# Attiny85_Blinking_Led_FIS2018.net
KiCad netlist of a schematic drawn in EAGLE
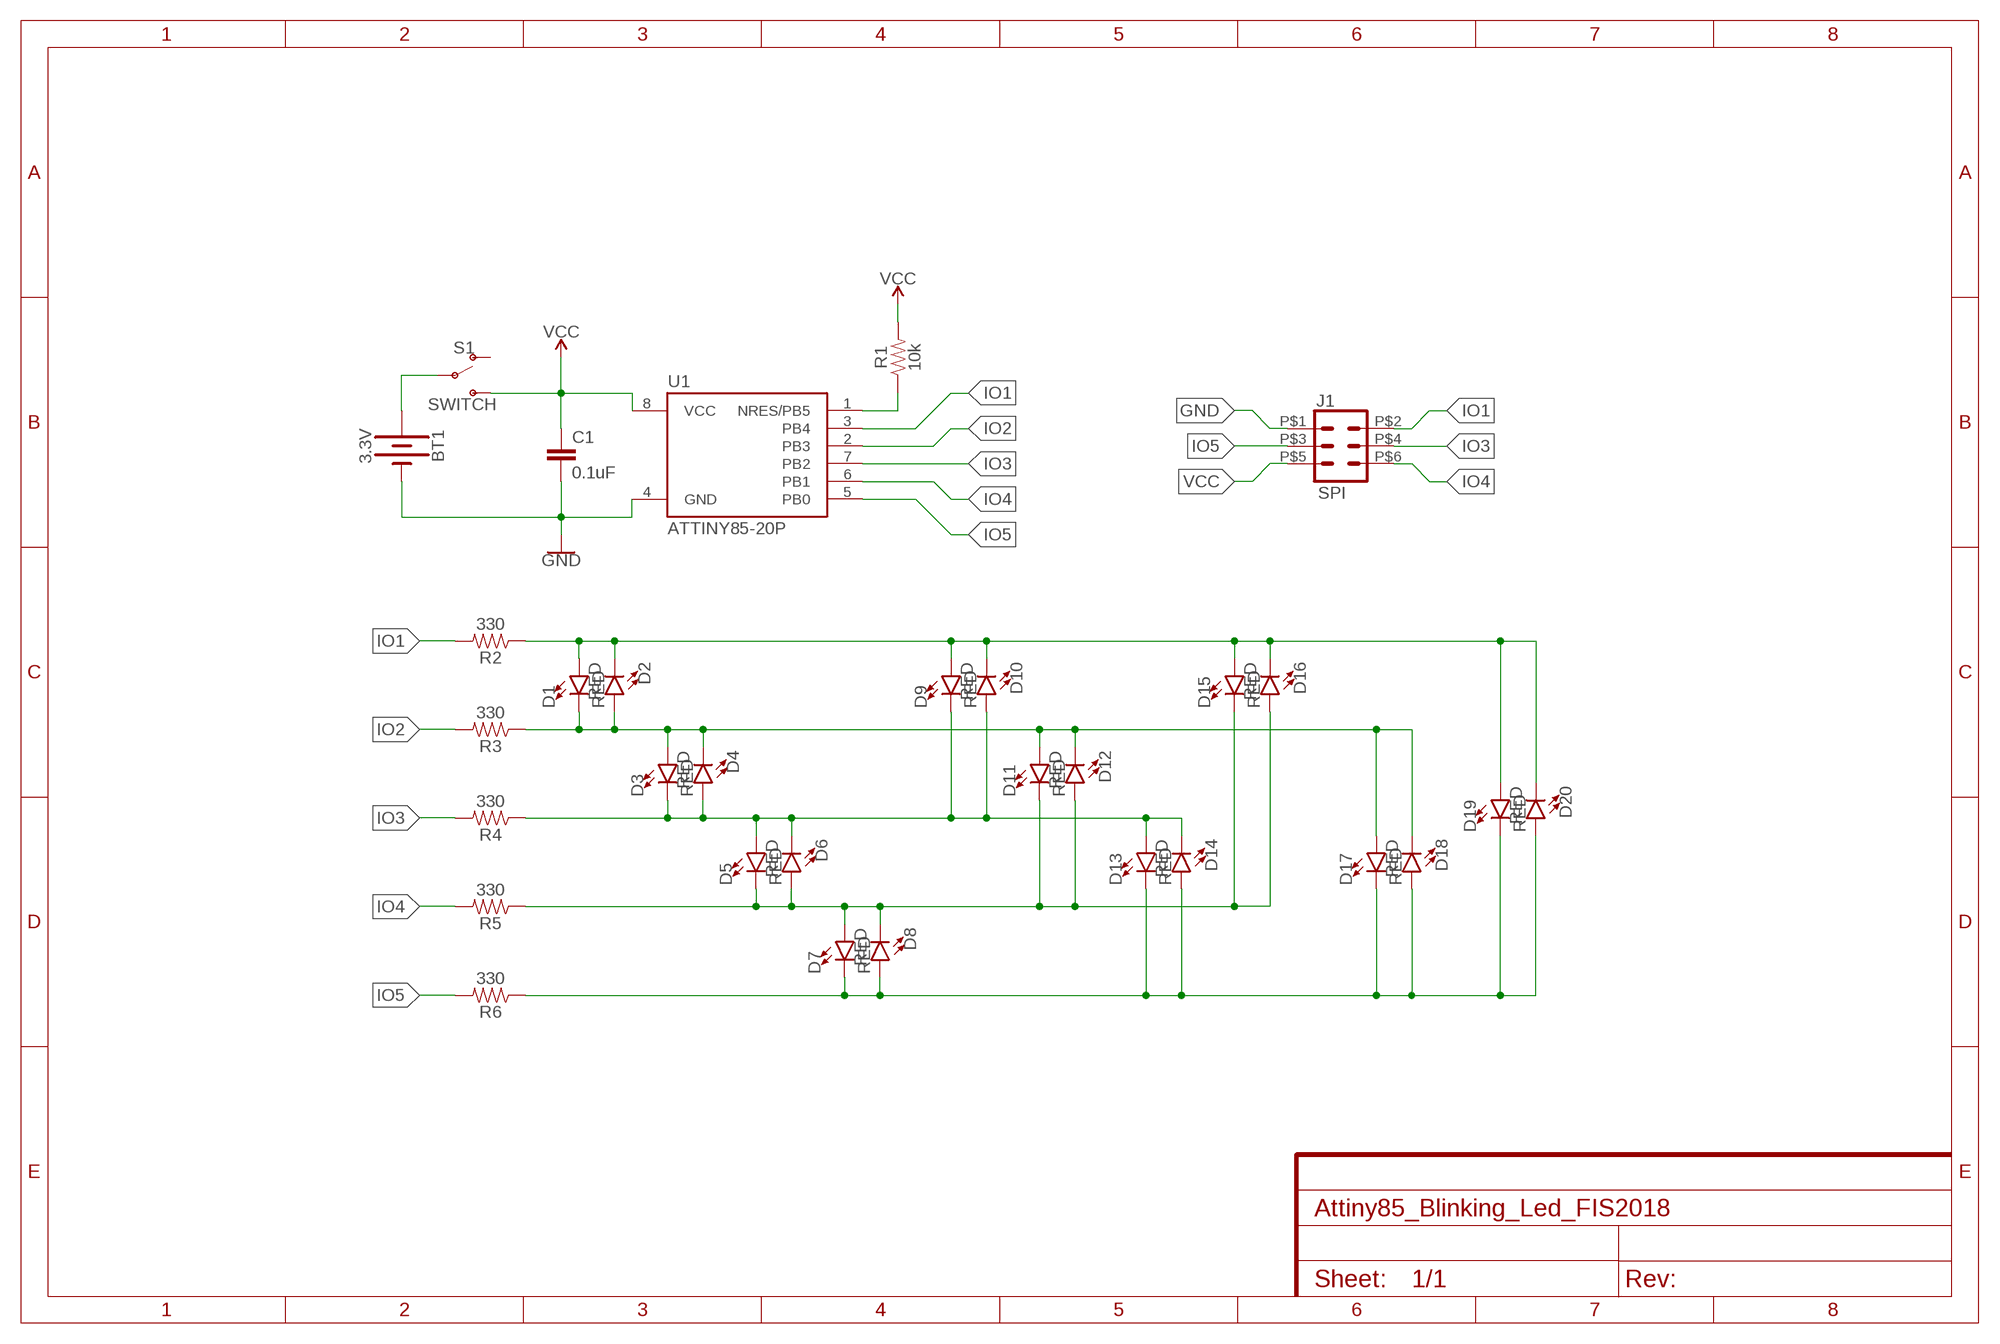
[diagram p0: schematic, sheet 1]

(export (version "E")
  (design (tool "Eeschema 10.0.6"))
  (components
    (comp (ref "BT1")
      (value "3.3V")
      (footprint "eagle-import:BATTCON_20MM_4LEGS")
      (libsource (lib "eagle-import") (part "BATTERY-20MM_SMD_4LEGS"))
    )
    (comp (ref "C1")
      (value "0.1uF")
      (footprint "eagle-import:0603")
      (libsource (lib "eagle-import") (part "0.1UF-0603-25V-(+80/-20%)"))
    )
    (comp (ref "D1")
      (value "RED")
      (footprint "eagle-import:LED_3MM")
      (libsource (lib "eagle-import") (part "LED3MM"))
    )
    (comp (ref "D2")
      (value "RED")
      (footprint "eagle-import:LED_3MM")
      (libsource (lib "eagle-import") (part "LED3MM"))
    )
    (comp (ref "D3")
      (value "RED")
      (footprint "eagle-import:LED_3MM")
      (libsource (lib "eagle-import") (part "LED3MM"))
    )
    (comp (ref "D4")
      (value "RED")
      (footprint "eagle-import:LED_3MM")
      (libsource (lib "eagle-import") (part "LED3MM"))
    )
    (comp (ref "D5")
      (value "RED")
      (footprint "eagle-import:LED_3MM")
      (libsource (lib "eagle-import") (part "LED3MM"))
    )
    (comp (ref "D6")
      (value "RED")
      (footprint "eagle-import:LED_3MM")
      (libsource (lib "eagle-import") (part "LED3MM"))
    )
    (comp (ref "D7")
      (value "RED")
      (footprint "eagle-import:LED_3MM")
      (libsource (lib "eagle-import") (part "LED3MM"))
    )
    (comp (ref "D8")
      (value "RED")
      (footprint "eagle-import:LED_3MM")
      (libsource (lib "eagle-import") (part "LED3MM"))
    )
    (comp (ref "D9")
      (value "RED")
      (footprint "eagle-import:LED_3MM")
      (libsource (lib "eagle-import") (part "LED3MM"))
    )
    (comp (ref "D10")
      (value "RED")
      (footprint "eagle-import:LED_3MM")
      (libsource (lib "eagle-import") (part "LED3MM"))
    )
    (comp (ref "D11")
      (value "RED")
      (footprint "eagle-import:LED_3MM")
      (libsource (lib "eagle-import") (part "LED3MM"))
    )
    (comp (ref "D12")
      (value "RED")
      (footprint "eagle-import:LED_3MM")
      (libsource (lib "eagle-import") (part "LED3MM"))
    )
    (comp (ref "D13")
      (value "RED")
      (footprint "eagle-import:LED_3MM")
      (libsource (lib "eagle-import") (part "LED3MM"))
    )
    (comp (ref "D14")
      (value "RED")
      (footprint "eagle-import:LED_3MM")
      (libsource (lib "eagle-import") (part "LED3MM"))
    )
    (comp (ref "D15")
      (value "RED")
      (footprint "eagle-import:LED_3MM")
      (libsource (lib "eagle-import") (part "LED3MM"))
    )
    (comp (ref "D16")
      (value "RED")
      (footprint "eagle-import:LED_3MM")
      (libsource (lib "eagle-import") (part "LED3MM"))
    )
    (comp (ref "D17")
      (value "RED")
      (footprint "eagle-import:LED_3MM")
      (libsource (lib "eagle-import") (part "LED3MM"))
    )
    (comp (ref "D18")
      (value "RED")
      (footprint "eagle-import:LED_3MM")
      (libsource (lib "eagle-import") (part "LED3MM"))
    )
    (comp (ref "D19")
      (value "RED")
      (footprint "eagle-import:LED_3MM")
      (libsource (lib "eagle-import") (part "LED3MM"))
    )
    (comp (ref "D20")
      (value "RED")
      (footprint "eagle-import:LED_3MM")
      (libsource (lib "eagle-import") (part "LED3MM"))
    )
    (comp (ref "J1")
      (value "SPI")
      (footprint "eagle-import:2X3_POGO")
      (libsource (lib "eagle-import") (part "CONN_03X2POGO_PINS"))
    )
    (comp (ref "R1")
      (value "10k")
      (footprint "eagle-import:AXIAL-0.3")
      (libsource (lib "eagle-import") (part "10KOHM-HORIZ-1/4W-1%"))
    )
    (comp (ref "R2")
      (value "330")
      (footprint "eagle-import:AXIAL-0.3")
      (libsource (lib "eagle-import") (part "10KOHM-HORIZ-1/4W-1%"))
    )
    (comp (ref "R3")
      (value "330")
      (footprint "eagle-import:AXIAL-0.3")
      (libsource (lib "eagle-import") (part "10KOHM-HORIZ-1/4W-1%"))
    )
    (comp (ref "R4")
      (value "330")
      (footprint "eagle-import:AXIAL-0.3")
      (libsource (lib "eagle-import") (part "10KOHM-HORIZ-1/4W-1%"))
    )
    (comp (ref "R5")
      (value "330")
      (footprint "eagle-import:AXIAL-0.3")
      (libsource (lib "eagle-import") (part "10KOHM-HORIZ-1/4W-1%"))
    )
    (comp (ref "R6")
      (value "330")
      (footprint "eagle-import:AXIAL-0.3")
      (libsource (lib "eagle-import") (part "10KOHM-HORIZ-1/4W-1%"))
    )
    (comp (ref "S1")
      (value "SWITCH")
      (footprint "eagle-import:SWITCH_SPST_SMD_A")
      (libsource (lib "eagle-import") (part "SWITCH-SPDT-SMD-RIGHT-ANGLE"))
    )
    (comp (ref "U1")
      (value "ATTINY85-20P")
      (footprint "eagle-import:PDIP08_300MIL")
      (libsource (lib "eagle-import") (part "ATTINY85P-20"))
    )
  )
  (nets
    (net (code "1") (name "GND") (class "Default")
      (node (ref "BT1") (pin "NEGATIVE") (pinfunction "-_NEGATIVE") (pintype "power_in"))
      (node (ref "C1") (pin "2") (pinfunction "2_2") (pintype "passive"))
      (node (ref "J1") (pin "P$1") (pinfunction "1_P$1") (pintype "bidirectional"))
      (node (ref "U1") (pin "4") (pinfunction "GND_4") (pintype "power_in"))
    )
    (net (code "2") (name "IO1") (class "Default")
      (node (ref "J1") (pin "P$2") (pinfunction "2_P$2") (pintype "bidirectional"))
      (node (ref "R2") (pin "P$2") (pinfunction "2_P$2") (pintype "passive"))
      (node (ref "U1") (pin "3") (pinfunction "PB4_3") (pintype "bidirectional"))
    )
    (net (code "3") (name "IO2") (class "Default")
      (node (ref "R3") (pin "P$2") (pinfunction "2_P$2") (pintype "passive"))
      (node (ref "U1") (pin "2") (pinfunction "PB3_2") (pintype "bidirectional"))
    )
    (net (code "4") (name "IO3") (class "Default")
      (node (ref "J1") (pin "P$4") (pinfunction "4_P$4") (pintype "bidirectional"))
      (node (ref "R4") (pin "P$2") (pinfunction "2_P$2") (pintype "passive"))
      (node (ref "U1") (pin "7") (pinfunction "PB2_7") (pintype "bidirectional"))
    )
    (net (code "5") (name "IO4") (class "Default")
      (node (ref "J1") (pin "P$6") (pinfunction "6_P$6") (pintype "bidirectional"))
      (node (ref "R5") (pin "P$2") (pinfunction "2_P$2") (pintype "passive"))
      (node (ref "U1") (pin "6") (pinfunction "PB1_6") (pintype "bidirectional"))
    )
    (net (code "6") (name "IO5") (class "Default")
      (node (ref "J1") (pin "P$3") (pinfunction "3_P$3") (pintype "bidirectional"))
      (node (ref "R6") (pin "P$2") (pinfunction "2_P$2") (pintype "passive"))
      (node (ref "U1") (pin "5") (pinfunction "PB0_5") (pintype "bidirectional"))
    )
    (net (code "7") (name "Net-(D1-C)") (class "Default")
      (node (ref "D1") (pin "K") (pinfunction "C_K") (pintype "passive"))
      (node (ref "D11") (pin "A") (pinfunction "A_A") (pintype "passive"))
      (node (ref "D12") (pin "K") (pinfunction "C_K") (pintype "passive"))
      (node (ref "D17") (pin "A") (pinfunction "A_A") (pintype "passive"))
      (node (ref "D18") (pin "K") (pinfunction "C_K") (pintype "passive"))
      (node (ref "D2") (pin "A") (pinfunction "A_A") (pintype "passive"))
      (node (ref "D3") (pin "A") (pinfunction "A_A") (pintype "passive"))
      (node (ref "D4") (pin "K") (pinfunction "C_K") (pintype "passive"))
      (node (ref "R3") (pin "P$1") (pinfunction "1_P$1") (pintype "passive"))
    )
    (net (code "8") (name "Net-(D10-C)") (class "Default")
      (node (ref "D1") (pin "A") (pinfunction "A_A") (pintype "passive"))
      (node (ref "D10") (pin "K") (pinfunction "C_K") (pintype "passive"))
      (node (ref "D15") (pin "A") (pinfunction "A_A") (pintype "passive"))
      (node (ref "D16") (pin "K") (pinfunction "C_K") (pintype "passive"))
      (node (ref "D19") (pin "A") (pinfunction "A_A") (pintype "passive"))
      (node (ref "D2") (pin "K") (pinfunction "C_K") (pintype "passive"))
      (node (ref "D20") (pin "K") (pinfunction "C_K") (pintype "passive"))
      (node (ref "D9") (pin "A") (pinfunction "A_A") (pintype "passive"))
      (node (ref "R2") (pin "P$1") (pinfunction "1_P$1") (pintype "passive"))
    )
    (net (code "9") (name "Net-(D11-C)") (class "Default")
      (node (ref "D11") (pin "K") (pinfunction "C_K") (pintype "passive"))
      (node (ref "D12") (pin "A") (pinfunction "A_A") (pintype "passive"))
      (node (ref "D15") (pin "K") (pinfunction "C_K") (pintype "passive"))
      (node (ref "D16") (pin "A") (pinfunction "A_A") (pintype "passive"))
      (node (ref "D5") (pin "K") (pinfunction "C_K") (pintype "passive"))
      (node (ref "D6") (pin "A") (pinfunction "A_A") (pintype "passive"))
      (node (ref "D7") (pin "A") (pinfunction "A_A") (pintype "passive"))
      (node (ref "D8") (pin "K") (pinfunction "C_K") (pintype "passive"))
      (node (ref "R5") (pin "P$1") (pinfunction "1_P$1") (pintype "passive"))
    )
    (net (code "10") (name "Net-(D13-C)") (class "Default")
      (node (ref "D13") (pin "K") (pinfunction "C_K") (pintype "passive"))
      (node (ref "D14") (pin "A") (pinfunction "A_A") (pintype "passive"))
      (node (ref "D17") (pin "K") (pinfunction "C_K") (pintype "passive"))
      (node (ref "D18") (pin "A") (pinfunction "A_A") (pintype "passive"))
      (node (ref "D19") (pin "K") (pinfunction "C_K") (pintype "passive"))
      (node (ref "D20") (pin "A") (pinfunction "A_A") (pintype "passive"))
      (node (ref "D7") (pin "K") (pinfunction "C_K") (pintype "passive"))
      (node (ref "D8") (pin "A") (pinfunction "A_A") (pintype "passive"))
      (node (ref "R6") (pin "P$1") (pinfunction "1_P$1") (pintype "passive"))
    )
    (net (code "11") (name "Net-(D14-C)") (class "Default")
      (node (ref "D10") (pin "A") (pinfunction "A_A") (pintype "passive"))
      (node (ref "D13") (pin "A") (pinfunction "A_A") (pintype "passive"))
      (node (ref "D14") (pin "K") (pinfunction "C_K") (pintype "passive"))
      (node (ref "D3") (pin "K") (pinfunction "C_K") (pintype "passive"))
      (node (ref "D4") (pin "A") (pinfunction "A_A") (pintype "passive"))
      (node (ref "D5") (pin "A") (pinfunction "A_A") (pintype "passive"))
      (node (ref "D6") (pin "K") (pinfunction "C_K") (pintype "passive"))
      (node (ref "D9") (pin "K") (pinfunction "C_K") (pintype "passive"))
      (node (ref "R4") (pin "P$1") (pinfunction "1_P$1") (pintype "passive"))
    )
    (net (code "12") (name "Net-(R1-1)") (class "Default")
      (node (ref "R1") (pin "P$1") (pinfunction "1_P$1") (pintype "passive"))
      (node (ref "U1") (pin "1") (pinfunction "NRES/PB5_1") (pintype "bidirectional"))
    )
    (net (code "13") (name "Net-(S1-P)") (class "Default")
      (node (ref "BT1") (pin "POSITIVE@1") (pinfunction "+_POSITIVE@1") (pintype "power_in"))
      (node (ref "BT1") (pin "POSITIVE@2") (pinfunction "+_POSITIVE@2") (pintype "power_in"))
      (node (ref "BT1") (pin "POSITIVE@3") (pinfunction "+_POSITIVE@3") (pintype "power_in"))
      (node (ref "BT1") (pin "POSITIVE@4") (pinfunction "+_POSITIVE@4") (pintype "power_in"))
      (node (ref "S1") (pin "2") (pinfunction "P_2") (pintype "passive"))
    )
    (net (code "14") (name "VCC") (class "Default")
      (node (ref "C1") (pin "1") (pinfunction "1_1") (pintype "passive"))
      (node (ref "J1") (pin "P$5") (pinfunction "5_P$5") (pintype "bidirectional"))
      (node (ref "R1") (pin "P$2") (pinfunction "2_P$2") (pintype "passive"))
      (node (ref "S1") (pin "3") (pinfunction "S_3") (pintype "passive"))
      (node (ref "U1") (pin "8") (pinfunction "VCC_8") (pintype "power_in"))
    )
    (net (code "15") (name "unconnected-(S1-O-Pad1)") (class "Default")
      (node (ref "S1") (pin "1") (pinfunction "O_1") (pintype "passive"))
    )
  )
)
